# version_1_2.net
KiCad netlist of a schematic drawn in EAGLE
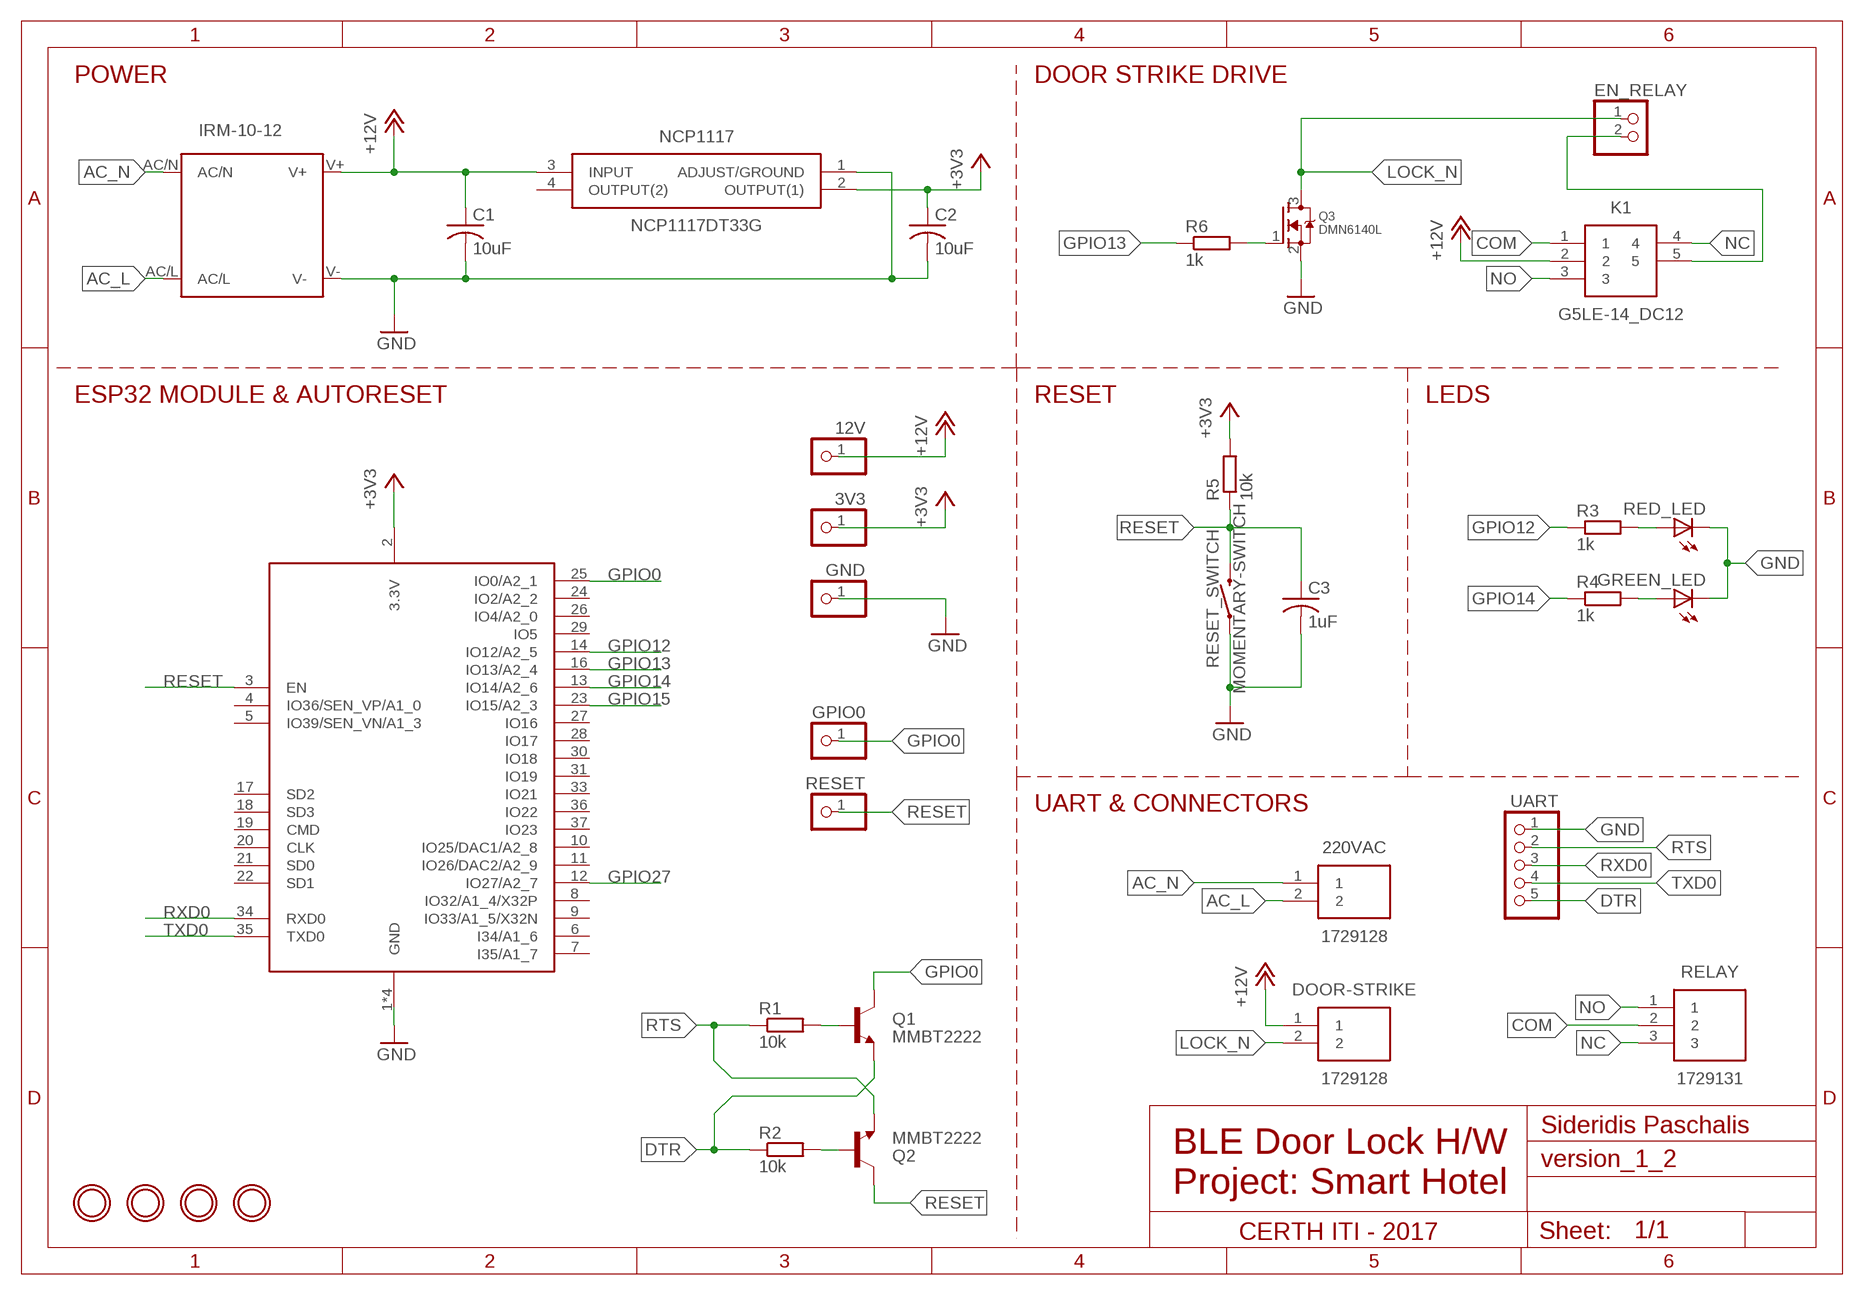
[diagram p0: schematic, sheet 1]

(export (version "E")
  (design (tool "Eeschema 10.0.6"))
  (components
    (comp (ref "3V3")
      (value "PINHD-1X1")
      (footprint "eagle-import:1X01")
      (libsource (lib "eagle-import") (part "PINHD-1X1"))
    )
    (comp (ref "12V")
      (value "PINHD-1X1")
      (footprint "eagle-import:1X01")
      (libsource (lib "eagle-import") (part "PINHD-1X1"))
    )
    (comp (ref "220VAC")
      (value "1729128")
      (footprint "eagle-import:HDRV2W110P0X508_1X2_1016X810X1")
      (fields (field (name "RS_PART_NUMBER") "1930586"))
      (libsource (lib "eagle-import") (part "1729128"))
    )
    (comp (ref "C1")
      (value "10uF")
      (footprint "eagle-import:C0805")
      (libsource (lib "eagle-import") (part "C-USC0805"))
    )
    (comp (ref "C2")
      (value "10uF")
      (footprint "eagle-import:C0805")
      (libsource (lib "eagle-import") (part "C-USC0805"))
    )
    (comp (ref "C3")
      (value "1uF")
      (footprint "eagle-import:C0805")
      (libsource (lib "eagle-import") (part "C-USC0805"))
    )
    (comp (ref "DOOR-STRIKE")
      (value "1729128")
      (footprint "eagle-import:HDRV2W110P0X508_1X2_1016X810X1")
      (fields (field (name "RS_PART_NUMBER") "1930586"))
      (libsource (lib "eagle-import") (part "1729128"))
    )
    (comp (ref "EN_RELAY")
      (value "PINHD-1X2")
      (footprint "eagle-import:1X02")
      (libsource (lib "eagle-import") (part "PINHD-1X2"))
    )
    (comp (ref "ESP32")
      (value "ESP32_WROOM32_SKINNY")
      (footprint "eagle-import:WROOM32_SKINNY")
      (libsource (lib "eagle-import") (part "ESP32_WROOM32_SKINNY"))
    )
    (comp (ref "GND")
      (value "PINHD-1X1")
      (footprint "eagle-import:1X01")
      (libsource (lib "eagle-import") (part "PINHD-1X1"))
    )
    (comp (ref "GPIO0")
      (value "PINHD-1X1")
      (footprint "eagle-import:1X01")
      (libsource (lib "eagle-import") (part "PINHD-1X1"))
    )
    (comp (ref "GREEN_LED")
      (value "LED5MM")
      (footprint "eagle-import:LED5MM")
      (libsource (lib "eagle-import") (part "LED5MM"))
    )
    (comp (ref "IRM-10-12")
      (value "IRM_05/10")
      (footprint "eagle-import:IRM_05_10")
      (libsource (lib "eagle-import") (part "IRM_05/10"))
    )
    (comp (ref "K1")
      (value "G5LE-14_DC12")
      (footprint "eagle-import:G5LE-1A")
      (fields (field (name "MANUFACTURER_PART_NUMBER") "G5LE-14 DC12"))
      (libsource (lib "eagle-import") (part "G5LE-14_DC12"))
    )
    (comp (ref "NCP1117")
      (value "NCP1117DT33G")
      (footprint "eagle-import:TO229P990X238-4N")
      (fields (field (name "RS_PART_NUMBER") "1023504"))
      (libsource (lib "eagle-import") (part "NCP1117DT33G"))
    )
    (comp (ref "Q1")
      (value "MMBT2222")
      (footprint "eagle-import:SOT23")
      (libsource (lib "eagle-import") (part "TRANSISTOR_NPNSOT23"))
    )
    (comp (ref "Q2")
      (value "MMBT2222")
      (footprint "eagle-import:SOT23")
      (libsource (lib "eagle-import") (part "TRANSISTOR_NPNSOT23"))
    )
    (comp (ref "Q3")
      (value "DMN6140L")
      (footprint "eagle-import:SOT23")
      (libsource (lib "eagle-import") (part "MOSFET-NREFLOW"))
    )
    (comp (ref "R1")
      (value "10k")
      (footprint "eagle-import:R0805")
      (libsource (lib "eagle-import") (part "R-EU_R0805"))
    )
    (comp (ref "R2")
      (value "10k")
      (footprint "eagle-import:R0805")
      (libsource (lib "eagle-import") (part "R-EU_R0805"))
    )
    (comp (ref "R3")
      (value "1k")
      (footprint "eagle-import:R0805")
      (libsource (lib "eagle-import") (part "R-EU_R0805"))
    )
    (comp (ref "R4")
      (value "1k")
      (footprint "eagle-import:R0805")
      (libsource (lib "eagle-import") (part "R-EU_R0805"))
    )
    (comp (ref "R5")
      (value "10k")
      (footprint "eagle-import:R0805")
      (libsource (lib "eagle-import") (part "R-EU_R0805"))
    )
    (comp (ref "R6")
      (value "1k")
      (footprint "eagle-import:R0805")
      (libsource (lib "eagle-import") (part "R-EU_R0805"))
    )
    (comp (ref "RED_LED")
      (value "LED5MM")
      (footprint "eagle-import:LED5MM")
      (libsource (lib "eagle-import") (part "LED5MM"))
    )
    (comp (ref "RELAY")
      (value "1729131")
      (footprint "eagle-import:SHDR3W110P0X508_1X3_1524X810X1")
      (fields (field (name "RS_PART_NUMBER") "1930592"))
      (libsource (lib "eagle-import") (part "1729131"))
    )
    (comp (ref "RESET")
      (value "PINHD-1X1")
      (footprint "eagle-import:1X01")
      (libsource (lib "eagle-import") (part "PINHD-1X1"))
    )
    (comp (ref "RESET_SWITCH")
      (value "MOMENTARY-SWITCH")
      (footprint "eagle-import:TACTILE_SWITCH_SMD_6.2MM_TALL")
      (libsource (lib "eagle-import") (part "MOMENTARY-SWITCH-SPST-SMD-6.2MM-TALL"))
    )
    (comp (ref "U$1")
      (value "MOUNTINGHOLE2.5")
      (footprint "eagle-import:MOUNTINGHOLE_2.5_PLATED")
      (libsource (lib "eagle-import") (part "MOUNTINGHOLE2.5"))
    )
    (comp (ref "U$2")
      (value "MOUNTINGHOLE2.5")
      (footprint "eagle-import:MOUNTINGHOLE_2.5_PLATED")
      (libsource (lib "eagle-import") (part "MOUNTINGHOLE2.5"))
    )
    (comp (ref "U$3")
      (value "MOUNTINGHOLE2.5")
      (footprint "eagle-import:MOUNTINGHOLE_2.5_PLATED")
      (libsource (lib "eagle-import") (part "MOUNTINGHOLE2.5"))
    )
    (comp (ref "U$4")
      (value "MOUNTINGHOLE2.5")
      (footprint "eagle-import:MOUNTINGHOLE_2.5_PLATED")
      (libsource (lib "eagle-import") (part "MOUNTINGHOLE2.5"))
    )
    (comp (ref "UART")
      (value "PINHD-1X5")
      (footprint "eagle-import:1X05")
      (libsource (lib "eagle-import") (part "PINHD-1X5"))
    )
  )
  (nets
    (net (code "1") (name "+3V3") (class "Default")
      (node (ref "3V3") (pin "1") (pinfunction "1_1") (pintype "passive"))
      (node (ref "C2") (pin "1") (pinfunction "1_1") (pintype "passive"))
      (node (ref "ESP32") (pin "2") (pinfunction "3.3V_2") (pintype "passive"))
      (node (ref "NCP1117") (pin "2") (pinfunction "OUTPUT(1)_2") (pintype "output"))
      (node (ref "R5") (pin "2") (pinfunction "2_2") (pintype "passive"))
    )
    (net (code "2") (name "+12V") (class "Default")
      (node (ref "12V") (pin "1") (pinfunction "1_1") (pintype "passive"))
      (node (ref "C1") (pin "1") (pinfunction "1_1") (pintype "passive"))
      (node (ref "DOOR-STRIKE") (pin "1") (pinfunction "1_1") (pintype "passive"))
      (node (ref "IRM-10-12") (pin "V+") (pinfunction "V+_V+") (pintype "output"))
      (node (ref "K1") (pin "2") (pinfunction "2_2") (pintype "passive"))
      (node (ref "NCP1117") (pin "3") (pinfunction "INPUT_3") (pintype "input"))
    )
    (net (code "3") (name "/GPIO15") (class "Default")
      (node (ref "ESP32") (pin "23") (pinfunction "IO15/A2_3_23") (pintype "bidirectional"))
    )
    (net (code "4") (name "/GPIO27") (class "Default")
      (node (ref "ESP32") (pin "12") (pinfunction "IO27/A2_7_12") (pintype "bidirectional"))
    )
    (net (code "5") (name "AC_L") (class "Default")
      (node (ref "220VAC") (pin "2") (pinfunction "2_2") (pintype "passive"))
      (node (ref "IRM-10-12") (pin "AC/L") (pinfunction "AC/L_AC/L") (pintype "input"))
    )
    (net (code "6") (name "AC_N") (class "Default")
      (node (ref "220VAC") (pin "1") (pinfunction "1_1") (pintype "passive"))
      (node (ref "IRM-10-12") (pin "AC/N") (pinfunction "AC/N_AC/N") (pintype "input"))
    )
    (net (code "7") (name "COM") (class "Default")
      (node (ref "K1") (pin "1") (pinfunction "1_1") (pintype "passive"))
      (node (ref "RELAY") (pin "2") (pinfunction "2_2") (pintype "passive"))
    )
    (net (code "8") (name "DTR") (class "Default")
      (node (ref "Q1") (pin "2") (pinfunction "E_2") (pintype "passive"))
      (node (ref "R2") (pin "1") (pinfunction "1_1") (pintype "passive"))
      (node (ref "UART") (pin "5") (pinfunction "5_5") (pintype "passive"))
    )
    (net (code "9") (name "GND") (class "Default")
      (node (ref "C1") (pin "2") (pinfunction "2_2") (pintype "passive"))
      (node (ref "C2") (pin "2") (pinfunction "2_2") (pintype "passive"))
      (node (ref "C3") (pin "2") (pinfunction "2_2") (pintype "passive"))
      (node (ref "ESP32") (pin "1") (pinfunction "GND_1") (pintype "passive"))
      (node (ref "ESP32") (pin "15") (pinfunction "GND_15") (pintype "passive"))
      (node (ref "ESP32") (pin "38") (pinfunction "GND_38") (pintype "passive"))
      (node (ref "ESP32") (pin "P$1") (pinfunction "GND_P$1") (pintype "passive"))
      (node (ref "GND") (pin "1") (pinfunction "1_1") (pintype "passive"))
      (node (ref "GREEN_LED") (pin "K") (pinfunction "C_K") (pintype "passive"))
      (node (ref "IRM-10-12") (pin "V-") (pinfunction "V-_V-") (pintype "output"))
      (node (ref "NCP1117") (pin "1") (pinfunction "ADJUST/GROUND_1") (pintype "passive"))
      (node (ref "Q3") (pin "2") (pinfunction "S_2") (pintype "bidirectional"))
      (node (ref "RED_LED") (pin "K") (pinfunction "C_K") (pintype "passive"))
      (node (ref "RESET_SWITCH") (pin "A2") (pinfunction "1_A2") (pintype "passive"))
      (node (ref "UART") (pin "1") (pinfunction "1_1") (pintype "passive"))
    )
    (net (code "10") (name "GPIO0") (class "Default")
      (node (ref "ESP32") (pin "25") (pinfunction "IO0/A2_1_25") (pintype "bidirectional"))
      (node (ref "GPIO0") (pin "1") (pinfunction "1_1") (pintype "passive"))
      (node (ref "Q1") (pin "3") (pinfunction "C_3") (pintype "passive"))
    )
    (net (code "11") (name "GPIO12") (class "Default")
      (node (ref "ESP32") (pin "14") (pinfunction "IO12/A2_5_14") (pintype "bidirectional"))
      (node (ref "R3") (pin "1") (pinfunction "1_1") (pintype "passive"))
    )
    (net (code "12") (name "GPIO13") (class "Default")
      (node (ref "ESP32") (pin "16") (pinfunction "IO13/A2_4_16") (pintype "bidirectional"))
      (node (ref "R6") (pin "1") (pinfunction "1_1") (pintype "passive"))
    )
    (net (code "13") (name "GPIO14") (class "Default")
      (node (ref "ESP32") (pin "13") (pinfunction "IO14/A2_6_13") (pintype "bidirectional"))
      (node (ref "R4") (pin "1") (pinfunction "1_1") (pintype "passive"))
    )
    (net (code "14") (name "LOCK_N") (class "Default")
      (node (ref "DOOR-STRIKE") (pin "2") (pinfunction "2_2") (pintype "passive"))
      (node (ref "EN_RELAY") (pin "1") (pinfunction "1_1") (pintype "passive"))
      (node (ref "Q3") (pin "3") (pinfunction "D_3") (pintype "bidirectional"))
    )
    (net (code "15") (name "NC") (class "Default")
      (node (ref "K1") (pin "4") (pinfunction "4_4") (pintype "passive"))
      (node (ref "RELAY") (pin "3") (pinfunction "3_3") (pintype "passive"))
    )
    (net (code "16") (name "NO") (class "Default")
      (node (ref "K1") (pin "3") (pinfunction "3_3") (pintype "passive"))
      (node (ref "RELAY") (pin "1") (pinfunction "1_1") (pintype "passive"))
    )
    (net (code "17") (name "Net-(EN_RELAY-Pad2)") (class "Default")
      (node (ref "EN_RELAY") (pin "2") (pinfunction "2_2") (pintype "passive"))
      (node (ref "K1") (pin "5") (pinfunction "5_5") (pintype "passive"))
    )
    (net (code "18") (name "Net-(GREEN_LED-PadA)") (class "Default")
      (node (ref "GREEN_LED") (pin "A") (pinfunction "A_A") (pintype "passive"))
      (node (ref "R4") (pin "2") (pinfunction "2_2") (pintype "passive"))
    )
    (net (code "19") (name "Net-(Q1-B)") (class "Default")
      (node (ref "Q1") (pin "1") (pinfunction "B_1") (pintype "passive"))
      (node (ref "R1") (pin "2") (pinfunction "2_2") (pintype "passive"))
    )
    (net (code "20") (name "Net-(Q2-B)") (class "Default")
      (node (ref "Q2") (pin "1") (pinfunction "B_1") (pintype "passive"))
      (node (ref "R2") (pin "2") (pinfunction "2_2") (pintype "passive"))
    )
    (net (code "21") (name "Net-(Q3-G)") (class "Default")
      (node (ref "Q3") (pin "1") (pinfunction "G_1") (pintype "bidirectional"))
      (node (ref "R6") (pin "2") (pinfunction "2_2") (pintype "passive"))
    )
    (net (code "22") (name "Net-(R3-Pad2)") (class "Default")
      (node (ref "R3") (pin "2") (pinfunction "2_2") (pintype "passive"))
      (node (ref "RED_LED") (pin "A") (pinfunction "A_A") (pintype "passive"))
    )
    (net (code "23") (name "RESET") (class "Default")
      (node (ref "C3") (pin "1") (pinfunction "1_1") (pintype "passive"))
      (node (ref "ESP32") (pin "3") (pinfunction "EN_3") (pintype "input"))
      (node (ref "Q2") (pin "3") (pinfunction "C_3") (pintype "passive"))
      (node (ref "R5") (pin "1") (pinfunction "1_1") (pintype "passive"))
      (node (ref "RESET") (pin "1") (pinfunction "1_1") (pintype "passive"))
      (node (ref "RESET_SWITCH") (pin "B2") (pinfunction "2_B2") (pintype "passive"))
    )
    (net (code "24") (name "RTS") (class "Default")
      (node (ref "Q2") (pin "2") (pinfunction "E_2") (pintype "passive"))
      (node (ref "R1") (pin "1") (pinfunction "1_1") (pintype "passive"))
      (node (ref "UART") (pin "2") (pinfunction "2_2") (pintype "passive"))
    )
    (net (code "25") (name "RXD0") (class "Default")
      (node (ref "ESP32") (pin "34") (pinfunction "RXD0_34") (pintype "input"))
      (node (ref "UART") (pin "3") (pinfunction "3_3") (pintype "passive"))
    )
    (net (code "26") (name "TXD0") (class "Default")
      (node (ref "ESP32") (pin "35") (pinfunction "TXD0_35") (pintype "output"))
      (node (ref "UART") (pin "4") (pinfunction "4_4") (pintype "passive"))
    )
    (net (code "27") (name "unconnected-(ESP32-CLK-Pad20)") (class "Default")
      (node (ref "ESP32") (pin "20") (pinfunction "CLK_20") (pintype "bidirectional"))
    )
    (net (code "28") (name "unconnected-(ESP32-CMD-Pad19)") (class "Default")
      (node (ref "ESP32") (pin "19") (pinfunction "CMD_19") (pintype "bidirectional"))
    )
    (net (code "29") (name "unconnected-(ESP32-I34{slash}A1_6-Pad6)") (class "Default")
      (node (ref "ESP32") (pin "6") (pinfunction "I34/A1_6_6") (pintype "bidirectional"))
    )
    (net (code "30") (name "unconnected-(ESP32-I35{slash}A1_7-Pad7)") (class "Default")
      (node (ref "ESP32") (pin "7") (pinfunction "I35/A1_7_7") (pintype "bidirectional"))
    )
    (net (code "31") (name "unconnected-(ESP32-IO2{slash}A2_2-Pad24)") (class "Default")
      (node (ref "ESP32") (pin "24") (pinfunction "IO2/A2_2_24") (pintype "bidirectional"))
    )
    (net (code "32") (name "unconnected-(ESP32-IO4{slash}A2_0-Pad26)") (class "Default")
      (node (ref "ESP32") (pin "26") (pinfunction "IO4/A2_0_26") (pintype "bidirectional"))
    )
    (net (code "33") (name "unconnected-(ESP32-IO5-Pad29)") (class "Default")
      (node (ref "ESP32") (pin "29") (pinfunction "IO5_29") (pintype "bidirectional"))
    )
    (net (code "34") (name "unconnected-(ESP32-IO16-Pad27)") (class "Default")
      (node (ref "ESP32") (pin "27") (pinfunction "IO16_27") (pintype "bidirectional"))
    )
    (net (code "35") (name "unconnected-(ESP32-IO17-Pad28)") (class "Default")
      (node (ref "ESP32") (pin "28") (pinfunction "IO17_28") (pintype "bidirectional"))
    )
    (net (code "36") (name "unconnected-(ESP32-IO18-Pad30)") (class "Default")
      (node (ref "ESP32") (pin "30") (pinfunction "IO18_30") (pintype "bidirectional"))
    )
    (net (code "37") (name "unconnected-(ESP32-IO19-Pad31)") (class "Default")
      (node (ref "ESP32") (pin "31") (pinfunction "IO19_31") (pintype "bidirectional"))
    )
    (net (code "38") (name "unconnected-(ESP32-IO21-Pad33)") (class "Default")
      (node (ref "ESP32") (pin "33") (pinfunction "IO21_33") (pintype "bidirectional"))
    )
    (net (code "39") (name "unconnected-(ESP32-IO22-Pad36)") (class "Default")
      (node (ref "ESP32") (pin "36") (pinfunction "IO22_36") (pintype "bidirectional"))
    )
    (net (code "40") (name "unconnected-(ESP32-IO23-Pad37)") (class "Default")
      (node (ref "ESP32") (pin "37") (pinfunction "IO23_37") (pintype "bidirectional"))
    )
    (net (code "41") (name "unconnected-(ESP32-IO25{slash}DAC1{slash}A2_8-Pad10)") (class "Default")
      (node (ref "ESP32") (pin "10") (pinfunction "IO25/DAC1/A2_8_10") (pintype "bidirectional"))
    )
    (net (code "42") (name "unconnected-(ESP32-IO26{slash}DAC2{slash}A2_9-Pad11)") (class "Default")
      (node (ref "ESP32") (pin "11") (pinfunction "IO26/DAC2/A2_9_11") (pintype "bidirectional"))
    )
    (net (code "43") (name "unconnected-(ESP32-IO32{slash}A1_4{slash}X32P-Pad8)") (class "Default")
      (node (ref "ESP32") (pin "8") (pinfunction "IO32/A1_4/X32P_8") (pintype "bidirectional"))
    )
    (net (code "44") (name "unconnected-(ESP32-IO33{slash}A1_5{slash}X32N-Pad9)") (class "Default")
      (node (ref "ESP32") (pin "9") (pinfunction "IO33/A1_5/X32N_9") (pintype "bidirectional"))
    )
    (net (code "45") (name "unconnected-(ESP32-IO36{slash}SEN_VP{slash}A1_0-Pad4)") (class "Default")
      (node (ref "ESP32") (pin "4") (pinfunction "IO36/SEN_VP/A1_0_4") (pintype "passive"))
    )
    (net (code "46") (name "unconnected-(ESP32-IO39{slash}SEN_VN{slash}A1_3-Pad5)") (class "Default")
      (node (ref "ESP32") (pin "5") (pinfunction "IO39/SEN_VN/A1_3_5") (pintype "passive"))
    )
    (net (code "47") (name "unconnected-(ESP32-SD0-Pad21)") (class "Default")
      (node (ref "ESP32") (pin "21") (pinfunction "SD0_21") (pintype "bidirectional"))
    )
    (net (code "48") (name "unconnected-(ESP32-SD1-Pad22)") (class "Default")
      (node (ref "ESP32") (pin "22") (pinfunction "SD1_22") (pintype "bidirectional"))
    )
    (net (code "49") (name "unconnected-(ESP32-SD2-Pad17)") (class "Default")
      (node (ref "ESP32") (pin "17") (pinfunction "SD2_17") (pintype "bidirectional"))
    )
    (net (code "50") (name "unconnected-(ESP32-SD3-Pad18)") (class "Default")
      (node (ref "ESP32") (pin "18") (pinfunction "SD3_18") (pintype "bidirectional"))
    )
    (net (code "51") (name "unconnected-(NCP1117-OUTPUT(2)-Pad4)") (class "Default")
      (node (ref "NCP1117") (pin "4") (pinfunction "OUTPUT(2)_4") (pintype "output"))
    )
  )
)
